# Daughter2.net
KiCad netlist of a schematic drawn in EAGLE
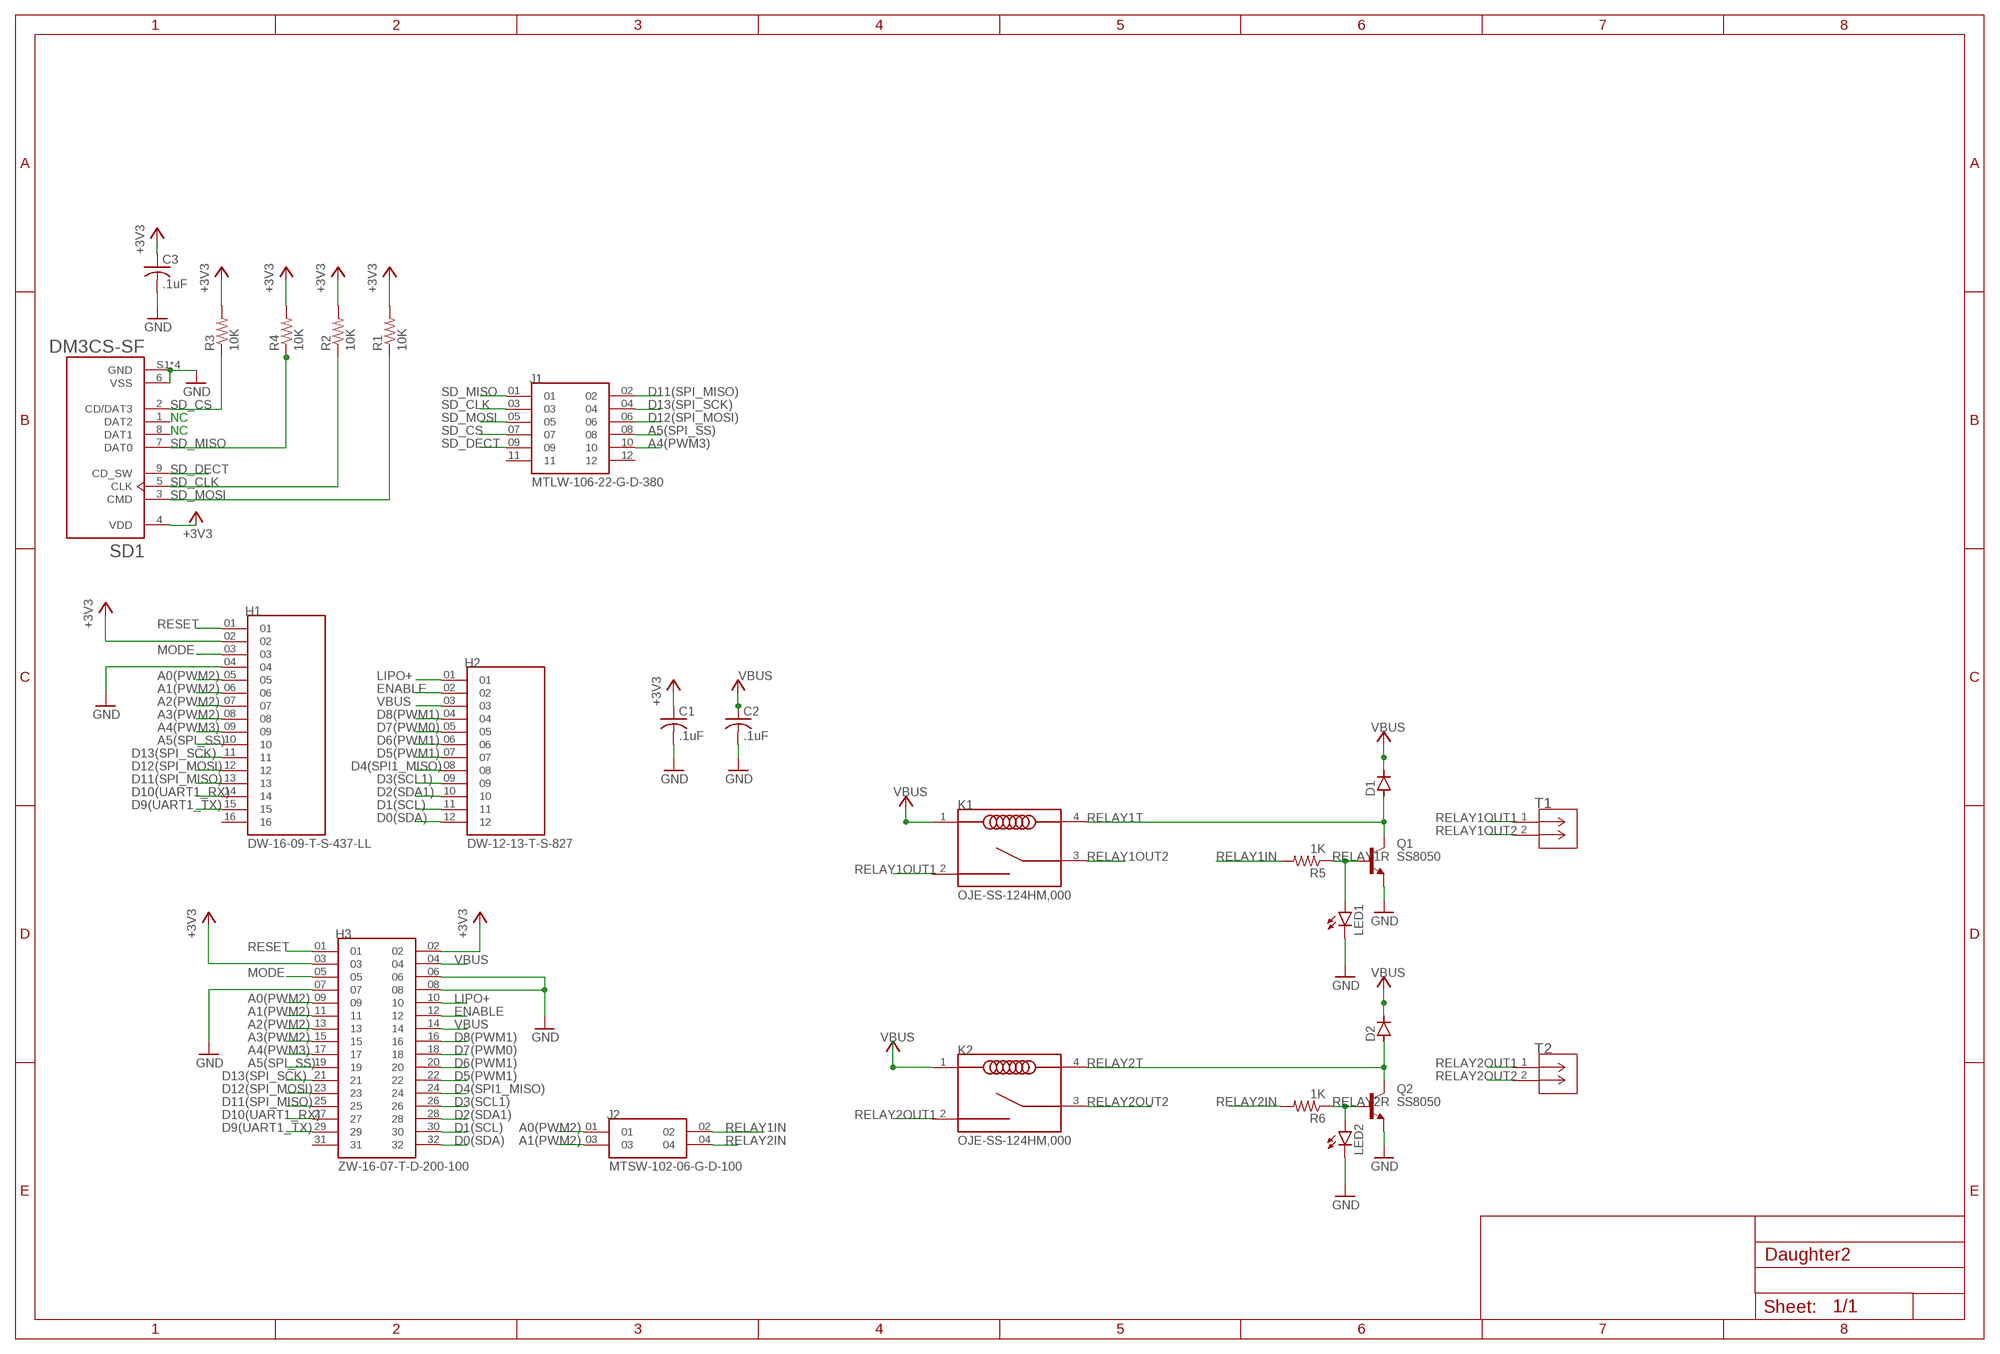
[diagram p0: schematic, sheet 1]

(export (version "E")
  (design (tool "Eeschema 10.0.6"))
  (components
    (comp (ref "C1")
      (value ".1uF")
      (footprint "eagle-import:C0805")
      (libsource (lib "eagle-import") (part "C-USC0805"))
    )
    (comp (ref "C2")
      (value ".1uF")
      (footprint "eagle-import:C0805")
      (libsource (lib "eagle-import") (part "C-USC0805"))
    )
    (comp (ref "C3")
      (value ".1uF")
      (footprint "eagle-import:C0805")
      (libsource (lib "eagle-import") (part "C-USC0805"))
    )
    (comp (ref "D1")
      (value "D-SOD-80")
      (footprint "eagle-import:SOD80")
      (libsource (lib "eagle-import") (part "D-SOD-80"))
    )
    (comp (ref "D2")
      (value "D-SOD-80")
      (footprint "eagle-import:SOD80")
      (libsource (lib "eagle-import") (part "D-SOD-80"))
    )
    (comp (ref "H1")
      (value "DW-16-09-T-S-437-LL")
      (footprint "eagle-import:SAMTEC_DW-16-09-T-S-437-LL")
      (fields (field (name "MF") "Samtec"))
      (libsource (lib "eagle-import") (part "DW-16-09-T-S-437-LL"))
    )
    (comp (ref "H2")
      (value "DW-12-13-T-S-827")
      (footprint "eagle-import:SAMTEC_DW-12-13-T-S-827")
      (fields (field (name "MF") "Samtec Inc."))
      (libsource (lib "eagle-import") (part "DW-12-13-T-S-827"))
    )
    (comp (ref "H3")
      (value "ZW-16-07-T-D-200-100")
      (footprint "eagle-import:SAMTEC_ZW-16-07-T-D-200-100")
      (fields (field (name "MF") "Samtec Inc."))
      (libsource (lib "eagle-import") (part "ZW-16-07-T-D-200-100"))
    )
    (comp (ref "J1")
      (value "MTLW-106-22-G-D-380")
      (footprint "eagle-import:SAMTEC_MTLW-106-22-G-D-380")
      (fields (field (name "MF") "Samtec"))
      (libsource (lib "eagle-import") (part "MTLW-106-22-G-D-380"))
    )
    (comp (ref "J2")
      (value "MTSW-102-06-G-D-100")
      (footprint "eagle-import:SAMTEC_MTSW-102-06-G-D-100")
      (fields (field (name "MF") "Samtec Inc."))
      (libsource (lib "eagle-import") (part "MTSW-102-06-G-D-100"))
    )
    (comp (ref "K1")
      (value "OJE-SS-124HM,000")
      (footprint "eagle-import:RELAY_OJE-SS-124HM,000")
      (fields (field (name "COMMENT") "6-1419128-4") (field (name "MF") "TE Connectivity"))
      (libsource (lib "eagle-import") (part "OJE-SS-124HM,000"))
    )
    (comp (ref "K2")
      (value "OJE-SS-124HM,000")
      (footprint "eagle-import:RELAY_OJE-SS-124HM,000")
      (fields (field (name "COMMENT") "6-1419128-4") (field (name "MF") "TE Connectivity"))
      (libsource (lib "eagle-import") (part "OJE-SS-124HM,000"))
    )
    (comp (ref "LED1")
      (value "LEDCHIP-LED0603")
      (footprint "eagle-import:CHIP-LED0603")
      (libsource (lib "eagle-import") (part "LEDCHIP-LED0603"))
    )
    (comp (ref "LED2")
      (value "LEDCHIP-LED0603")
      (footprint "eagle-import:CHIP-LED0603")
      (libsource (lib "eagle-import") (part "LEDCHIP-LED0603"))
    )
    (comp (ref "Q1")
      (value "SS8050")
      (footprint "eagle-import:SOT-23_BEC")
      (fields (field (name "MF") "Microdiode Electronics"))
      (libsource (lib "eagle-import") (part "SS8050"))
    )
    (comp (ref "Q2")
      (value "SS8050")
      (footprint "eagle-import:SOT-23_BEC")
      (fields (field (name "MF") "Microdiode Electronics"))
      (libsource (lib "eagle-import") (part "SS8050"))
    )
    (comp (ref "R1")
      (value "10K")
      (footprint "eagle-import:R0805")
      (libsource (lib "eagle-import") (part "R-US_R0805"))
    )
    (comp (ref "R2")
      (value "10K")
      (footprint "eagle-import:R0805")
      (libsource (lib "eagle-import") (part "R-US_R0805"))
    )
    (comp (ref "R3")
      (value "10K")
      (footprint "eagle-import:R0805")
      (libsource (lib "eagle-import") (part "R-US_R0805"))
    )
    (comp (ref "R4")
      (value "10K")
      (footprint "eagle-import:R0805")
      (libsource (lib "eagle-import") (part "R-US_R0805"))
    )
    (comp (ref "R5")
      (value "1K")
      (footprint "eagle-import:R0805")
      (libsource (lib "eagle-import") (part "R-US_R0805"))
    )
    (comp (ref "R6")
      (value "1K")
      (footprint "eagle-import:R0805")
      (libsource (lib "eagle-import") (part "R-US_R0805"))
    )
    (comp (ref "SD1")
      (value "DM3CS-SF")
      (footprint "eagle-import:HRS_DM3CS-SF")
      (fields (field (name "MF") "Hirose"))
      (libsource (lib "eagle-import") (part "DM3CS-SF"))
    )
    (comp (ref "T1")
      (value "OSTVN02A150")
      (footprint "eagle-import:CONN_OSTVN02A150_OST")
      (fields (field (name "COPYRIGHT") "Copyright (C) 2022 Ultra Librarian. All rights reserved."))
      (libsource (lib "eagle-import") (part "OSTVN02A150"))
    )
    (comp (ref "T2")
      (value "OSTVN02A150")
      (footprint "eagle-import:CONN_OSTVN02A150_OST")
      (fields (field (name "COPYRIGHT") "Copyright (C) 2022 Ultra Librarian. All rights reserved."))
      (libsource (lib "eagle-import") (part "OSTVN02A150"))
    )
  )
  (nets
    (net (code "1") (name "+3V3") (class "Default")
      (node (ref "C1") (pin "1") (pinfunction "1_1") (pintype "passive"))
      (node (ref "C3") (pin "1") (pinfunction "1_1") (pintype "passive"))
      (node (ref "H1") (pin "02") (pinfunction "02_02") (pintype "passive"))
      (node (ref "H3") (pin "02") (pinfunction "02_02") (pintype "passive"))
      (node (ref "H3") (pin "03") (pinfunction "03_03") (pintype "passive"))
      (node (ref "R1") (pin "2") (pinfunction "2_2") (pintype "passive"))
      (node (ref "R2") (pin "2") (pinfunction "2_2") (pintype "passive"))
      (node (ref "R3") (pin "2") (pinfunction "2_2") (pintype "passive"))
      (node (ref "R4") (pin "2") (pinfunction "2_2") (pintype "passive"))
      (node (ref "SD1") (pin "4") (pinfunction "VDD_4") (pintype "passive"))
    )
    (net (code "2") (name "/A0(PWM2)") (class "Default")
      (node (ref "H1") (pin "05") (pinfunction "05_05") (pintype "passive"))
      (node (ref "H3") (pin "09") (pinfunction "09_09") (pintype "passive"))
      (node (ref "J2") (pin "01") (pinfunction "01_01") (pintype "passive"))
    )
    (net (code "3") (name "/A1(PWM2)") (class "Default")
      (node (ref "H1") (pin "06") (pinfunction "06_06") (pintype "passive"))
      (node (ref "H3") (pin "11") (pinfunction "11_11") (pintype "passive"))
      (node (ref "J2") (pin "03") (pinfunction "03_03") (pintype "passive"))
    )
    (net (code "4") (name "/A2(PWM2)") (class "Default")
      (node (ref "H1") (pin "07") (pinfunction "07_07") (pintype "passive"))
      (node (ref "H3") (pin "13") (pinfunction "13_13") (pintype "passive"))
    )
    (net (code "5") (name "/A3(PWM2)") (class "Default")
      (node (ref "H1") (pin "08") (pinfunction "08_08") (pintype "passive"))
      (node (ref "H3") (pin "15") (pinfunction "15_15") (pintype "passive"))
    )
    (net (code "6") (name "/A4(PWM3)") (class "Default")
      (node (ref "H1") (pin "09") (pinfunction "09_09") (pintype "passive"))
      (node (ref "H3") (pin "17") (pinfunction "17_17") (pintype "passive"))
      (node (ref "J1") (pin "10") (pinfunction "10_10") (pintype "passive"))
    )
    (net (code "7") (name "/A5(SPI_SS)") (class "Default")
      (node (ref "H1") (pin "10") (pinfunction "10_10") (pintype "passive"))
      (node (ref "H3") (pin "19") (pinfunction "19_19") (pintype "passive"))
      (node (ref "J1") (pin "08") (pinfunction "08_08") (pintype "passive"))
    )
    (net (code "8") (name "/D0(SDA)") (class "Default")
      (node (ref "H2") (pin "12") (pinfunction "12_12") (pintype "passive"))
      (node (ref "H3") (pin "32") (pinfunction "32_32") (pintype "passive"))
    )
    (net (code "9") (name "/D1(SCL)") (class "Default")
      (node (ref "H2") (pin "11") (pinfunction "11_11") (pintype "passive"))
      (node (ref "H3") (pin "30") (pinfunction "30_30") (pintype "passive"))
    )
    (net (code "10") (name "/D2(SDA1)") (class "Default")
      (node (ref "H2") (pin "10") (pinfunction "10_10") (pintype "passive"))
      (node (ref "H3") (pin "28") (pinfunction "28_28") (pintype "passive"))
    )
    (net (code "11") (name "/D3(SCL1)") (class "Default")
      (node (ref "H2") (pin "09") (pinfunction "09_09") (pintype "passive"))
      (node (ref "H3") (pin "26") (pinfunction "26_26") (pintype "passive"))
    )
    (net (code "12") (name "/D4(SPI1_MISO)") (class "Default")
      (node (ref "H2") (pin "08") (pinfunction "08_08") (pintype "passive"))
      (node (ref "H3") (pin "24") (pinfunction "24_24") (pintype "passive"))
    )
    (net (code "13") (name "/D5(PWM1)") (class "Default")
      (node (ref "H2") (pin "07") (pinfunction "07_07") (pintype "passive"))
      (node (ref "H3") (pin "22") (pinfunction "22_22") (pintype "passive"))
    )
    (net (code "14") (name "/D6(PWM1)") (class "Default")
      (node (ref "H2") (pin "06") (pinfunction "06_06") (pintype "passive"))
      (node (ref "H3") (pin "20") (pinfunction "20_20") (pintype "passive"))
    )
    (net (code "15") (name "/D7(PWM0)") (class "Default")
      (node (ref "H2") (pin "05") (pinfunction "05_05") (pintype "passive"))
      (node (ref "H3") (pin "18") (pinfunction "18_18") (pintype "passive"))
    )
    (net (code "16") (name "/D8(PWM1)") (class "Default")
      (node (ref "H2") (pin "04") (pinfunction "04_04") (pintype "passive"))
      (node (ref "H3") (pin "16") (pinfunction "16_16") (pintype "passive"))
    )
    (net (code "17") (name "/D9(UART1_TX)") (class "Default")
      (node (ref "H1") (pin "15") (pinfunction "15_15") (pintype "passive"))
      (node (ref "H3") (pin "29") (pinfunction "29_29") (pintype "passive"))
    )
    (net (code "18") (name "/D10(UART1_RX)") (class "Default")
      (node (ref "H1") (pin "14") (pinfunction "14_14") (pintype "passive"))
      (node (ref "H3") (pin "27") (pinfunction "27_27") (pintype "passive"))
    )
    (net (code "19") (name "/D11(SPI_MISO)") (class "Default")
      (node (ref "H1") (pin "13") (pinfunction "13_13") (pintype "passive"))
      (node (ref "H3") (pin "25") (pinfunction "25_25") (pintype "passive"))
      (node (ref "J1") (pin "02") (pinfunction "02_02") (pintype "passive"))
    )
    (net (code "20") (name "/D12(SPI_MOSI)") (class "Default")
      (node (ref "H1") (pin "12") (pinfunction "12_12") (pintype "passive"))
      (node (ref "H3") (pin "23") (pinfunction "23_23") (pintype "passive"))
      (node (ref "J1") (pin "06") (pinfunction "06_06") (pintype "passive"))
    )
    (net (code "21") (name "/D13(SPI_SCK)") (class "Default")
      (node (ref "H1") (pin "11") (pinfunction "11_11") (pintype "passive"))
      (node (ref "H3") (pin "21") (pinfunction "21_21") (pintype "passive"))
      (node (ref "J1") (pin "04") (pinfunction "04_04") (pintype "passive"))
    )
    (net (code "22") (name "/ENABLE") (class "Default")
      (node (ref "H2") (pin "02") (pinfunction "02_02") (pintype "passive"))
      (node (ref "H3") (pin "12") (pinfunction "12_12") (pintype "passive"))
    )
    (net (code "23") (name "/LIPO+") (class "Default")
      (node (ref "H2") (pin "01") (pinfunction "01_01") (pintype "passive"))
      (node (ref "H3") (pin "10") (pinfunction "10_10") (pintype "passive"))
    )
    (net (code "24") (name "/MODE") (class "Default")
      (node (ref "H1") (pin "03") (pinfunction "03_03") (pintype "passive"))
      (node (ref "H3") (pin "05") (pinfunction "05_05") (pintype "passive"))
    )
    (net (code "25") (name "/RELAY1IN") (class "Default")
      (node (ref "J2") (pin "02") (pinfunction "02_02") (pintype "passive"))
      (node (ref "R5") (pin "2") (pinfunction "2_2") (pintype "passive"))
    )
    (net (code "26") (name "/RELAY1OUT1") (class "Default")
      (node (ref "K1") (pin "2") (pinfunction "2_2") (pintype "passive"))
      (node (ref "T1") (pin "1") (pinfunction "1_1") (pintype "passive"))
    )
    (net (code "27") (name "/RELAY1OUT2") (class "Default")
      (node (ref "K1") (pin "3") (pinfunction "3_3") (pintype "passive"))
      (node (ref "T1") (pin "2") (pinfunction "2_2") (pintype "passive"))
    )
    (net (code "28") (name "/RELAY1R") (class "Default")
      (node (ref "LED1") (pin "A") (pinfunction "A_A") (pintype "passive"))
      (node (ref "Q1") (pin "B") (pinfunction "B_B") (pintype "passive"))
      (node (ref "R5") (pin "1") (pinfunction "1_1") (pintype "passive"))
    )
    (net (code "29") (name "/RELAY1T") (class "Default")
      (node (ref "D1") (pin "2") (pinfunction "A_2") (pintype "passive"))
      (node (ref "K1") (pin "4") (pinfunction "4_4") (pintype "passive"))
      (node (ref "Q1") (pin "C") (pinfunction "C_C") (pintype "passive"))
    )
    (net (code "30") (name "/RELAY2IN") (class "Default")
      (node (ref "J2") (pin "04") (pinfunction "04_04") (pintype "passive"))
      (node (ref "R6") (pin "2") (pinfunction "2_2") (pintype "passive"))
    )
    (net (code "31") (name "/RELAY2OUT1") (class "Default")
      (node (ref "K2") (pin "2") (pinfunction "2_2") (pintype "passive"))
      (node (ref "T2") (pin "1") (pinfunction "1_1") (pintype "passive"))
    )
    (net (code "32") (name "/RELAY2OUT2") (class "Default")
      (node (ref "K2") (pin "3") (pinfunction "3_3") (pintype "passive"))
      (node (ref "T2") (pin "2") (pinfunction "2_2") (pintype "passive"))
    )
    (net (code "33") (name "/RELAY2R") (class "Default")
      (node (ref "LED2") (pin "A") (pinfunction "A_A") (pintype "passive"))
      (node (ref "Q2") (pin "B") (pinfunction "B_B") (pintype "passive"))
      (node (ref "R6") (pin "1") (pinfunction "1_1") (pintype "passive"))
    )
    (net (code "34") (name "/RELAY2T") (class "Default")
      (node (ref "D2") (pin "2") (pinfunction "A_2") (pintype "passive"))
      (node (ref "K2") (pin "4") (pinfunction "4_4") (pintype "passive"))
      (node (ref "Q2") (pin "C") (pinfunction "C_C") (pintype "passive"))
    )
    (net (code "35") (name "/RESET") (class "Default")
      (node (ref "H1") (pin "01") (pinfunction "01_01") (pintype "passive"))
      (node (ref "H3") (pin "01") (pinfunction "01_01") (pintype "passive"))
    )
    (net (code "36") (name "/SD_CLK") (class "Default")
      (node (ref "J1") (pin "03") (pinfunction "03_03") (pintype "passive"))
      (node (ref "R2") (pin "1") (pinfunction "1_1") (pintype "passive"))
      (node (ref "SD1") (pin "5") (pinfunction "CLK_5") (pintype "passive"))
    )
    (net (code "37") (name "/SD_CS") (class "Default")
      (node (ref "J1") (pin "07") (pinfunction "07_07") (pintype "passive"))
      (node (ref "R3") (pin "1") (pinfunction "1_1") (pintype "passive"))
      (node (ref "SD1") (pin "2") (pinfunction "CD/DAT3_2") (pintype "passive"))
    )
    (net (code "38") (name "/SD_DECT") (class "Default")
      (node (ref "J1") (pin "09") (pinfunction "09_09") (pintype "passive"))
      (node (ref "SD1") (pin "9") (pinfunction "CD_SW_9") (pintype "passive"))
    )
    (net (code "39") (name "/SD_MISO") (class "Default")
      (node (ref "J1") (pin "01") (pinfunction "01_01") (pintype "passive"))
      (node (ref "R4") (pin "1") (pinfunction "1_1") (pintype "passive"))
      (node (ref "SD1") (pin "7") (pinfunction "DAT0_7") (pintype "passive"))
    )
    (net (code "40") (name "/SD_MOSI") (class "Default")
      (node (ref "J1") (pin "05") (pinfunction "05_05") (pintype "passive"))
      (node (ref "R1") (pin "1") (pinfunction "1_1") (pintype "passive"))
      (node (ref "SD1") (pin "3") (pinfunction "CMD_3") (pintype "passive"))
    )
    (net (code "41") (name "GND") (class "Default")
      (node (ref "C1") (pin "2") (pinfunction "2_2") (pintype "passive"))
      (node (ref "C2") (pin "2") (pinfunction "2_2") (pintype "passive"))
      (node (ref "C3") (pin "2") (pinfunction "2_2") (pintype "passive"))
      (node (ref "H1") (pin "04") (pinfunction "04_04") (pintype "passive"))
      (node (ref "H3") (pin "06") (pinfunction "06_06") (pintype "passive"))
      (node (ref "H3") (pin "07") (pinfunction "07_07") (pintype "passive"))
      (node (ref "H3") (pin "08") (pinfunction "08_08") (pintype "passive"))
      (node (ref "LED1") (pin "C") (pinfunction "C_C") (pintype "passive"))
      (node (ref "LED2") (pin "C") (pinfunction "C_C") (pintype "passive"))
      (node (ref "Q1") (pin "E") (pinfunction "E_E") (pintype "passive"))
      (node (ref "Q2") (pin "E") (pinfunction "E_E") (pintype "passive"))
      (node (ref "SD1") (pin "6") (pinfunction "VSS_6") (pintype "passive"))
      (node (ref "SD1") (pin "S1") (pinfunction "GND_S1") (pintype "passive"))
      (node (ref "SD1") (pin "S2") (pinfunction "GND_S2") (pintype "passive"))
      (node (ref "SD1") (pin "S3") (pinfunction "GND_S3") (pintype "passive"))
      (node (ref "SD1") (pin "S5") (pinfunction "GND_S5") (pintype "passive"))
    )
    (net (code "42") (name "VCC") (class "Default")
      (node (ref "C2") (pin "1") (pinfunction "1_1") (pintype "passive"))
      (node (ref "D1") (pin "1") (pinfunction "C_1") (pintype "passive"))
      (node (ref "D2") (pin "1") (pinfunction "C_1") (pintype "passive"))
      (node (ref "H2") (pin "03") (pinfunction "03_03") (pintype "passive"))
      (node (ref "H3") (pin "04") (pinfunction "04_04") (pintype "passive"))
      (node (ref "H3") (pin "14") (pinfunction "14_14") (pintype "passive"))
      (node (ref "K1") (pin "1") (pinfunction "1_1") (pintype "passive"))
      (node (ref "K2") (pin "1") (pinfunction "1_1") (pintype "passive"))
    )
    (net (code "43") (name "unconnected-(H1-Pad16)") (class "Default")
      (node (ref "H1") (pin "16") (pinfunction "16_16") (pintype "passive"))
    )
    (net (code "44") (name "unconnected-(H3-Pad31)") (class "Default")
      (node (ref "H3") (pin "31") (pinfunction "31_31") (pintype "passive"))
    )
    (net (code "45") (name "unconnected-(J1-Pad11)") (class "Default")
      (node (ref "J1") (pin "11") (pinfunction "11_11") (pintype "passive"))
    )
    (net (code "46") (name "unconnected-(J1-Pad12)") (class "Default")
      (node (ref "J1") (pin "12") (pinfunction "12_12") (pintype "passive"))
    )
    (net (code "47") (name "unconnected-(SD1-DAT1-Pad8)") (class "Default")
      (node (ref "SD1") (pin "8") (pinfunction "DAT1_8") (pintype "passive"))
    )
    (net (code "48") (name "unconnected-(SD1-DAT2-Pad1)") (class "Default")
      (node (ref "SD1") (pin "1") (pinfunction "DAT2_1") (pintype "passive"))
    )
  )
)
